# 20240714_smart_wheelchair.net
KiCad netlist of a schematic drawn in Altium Designer
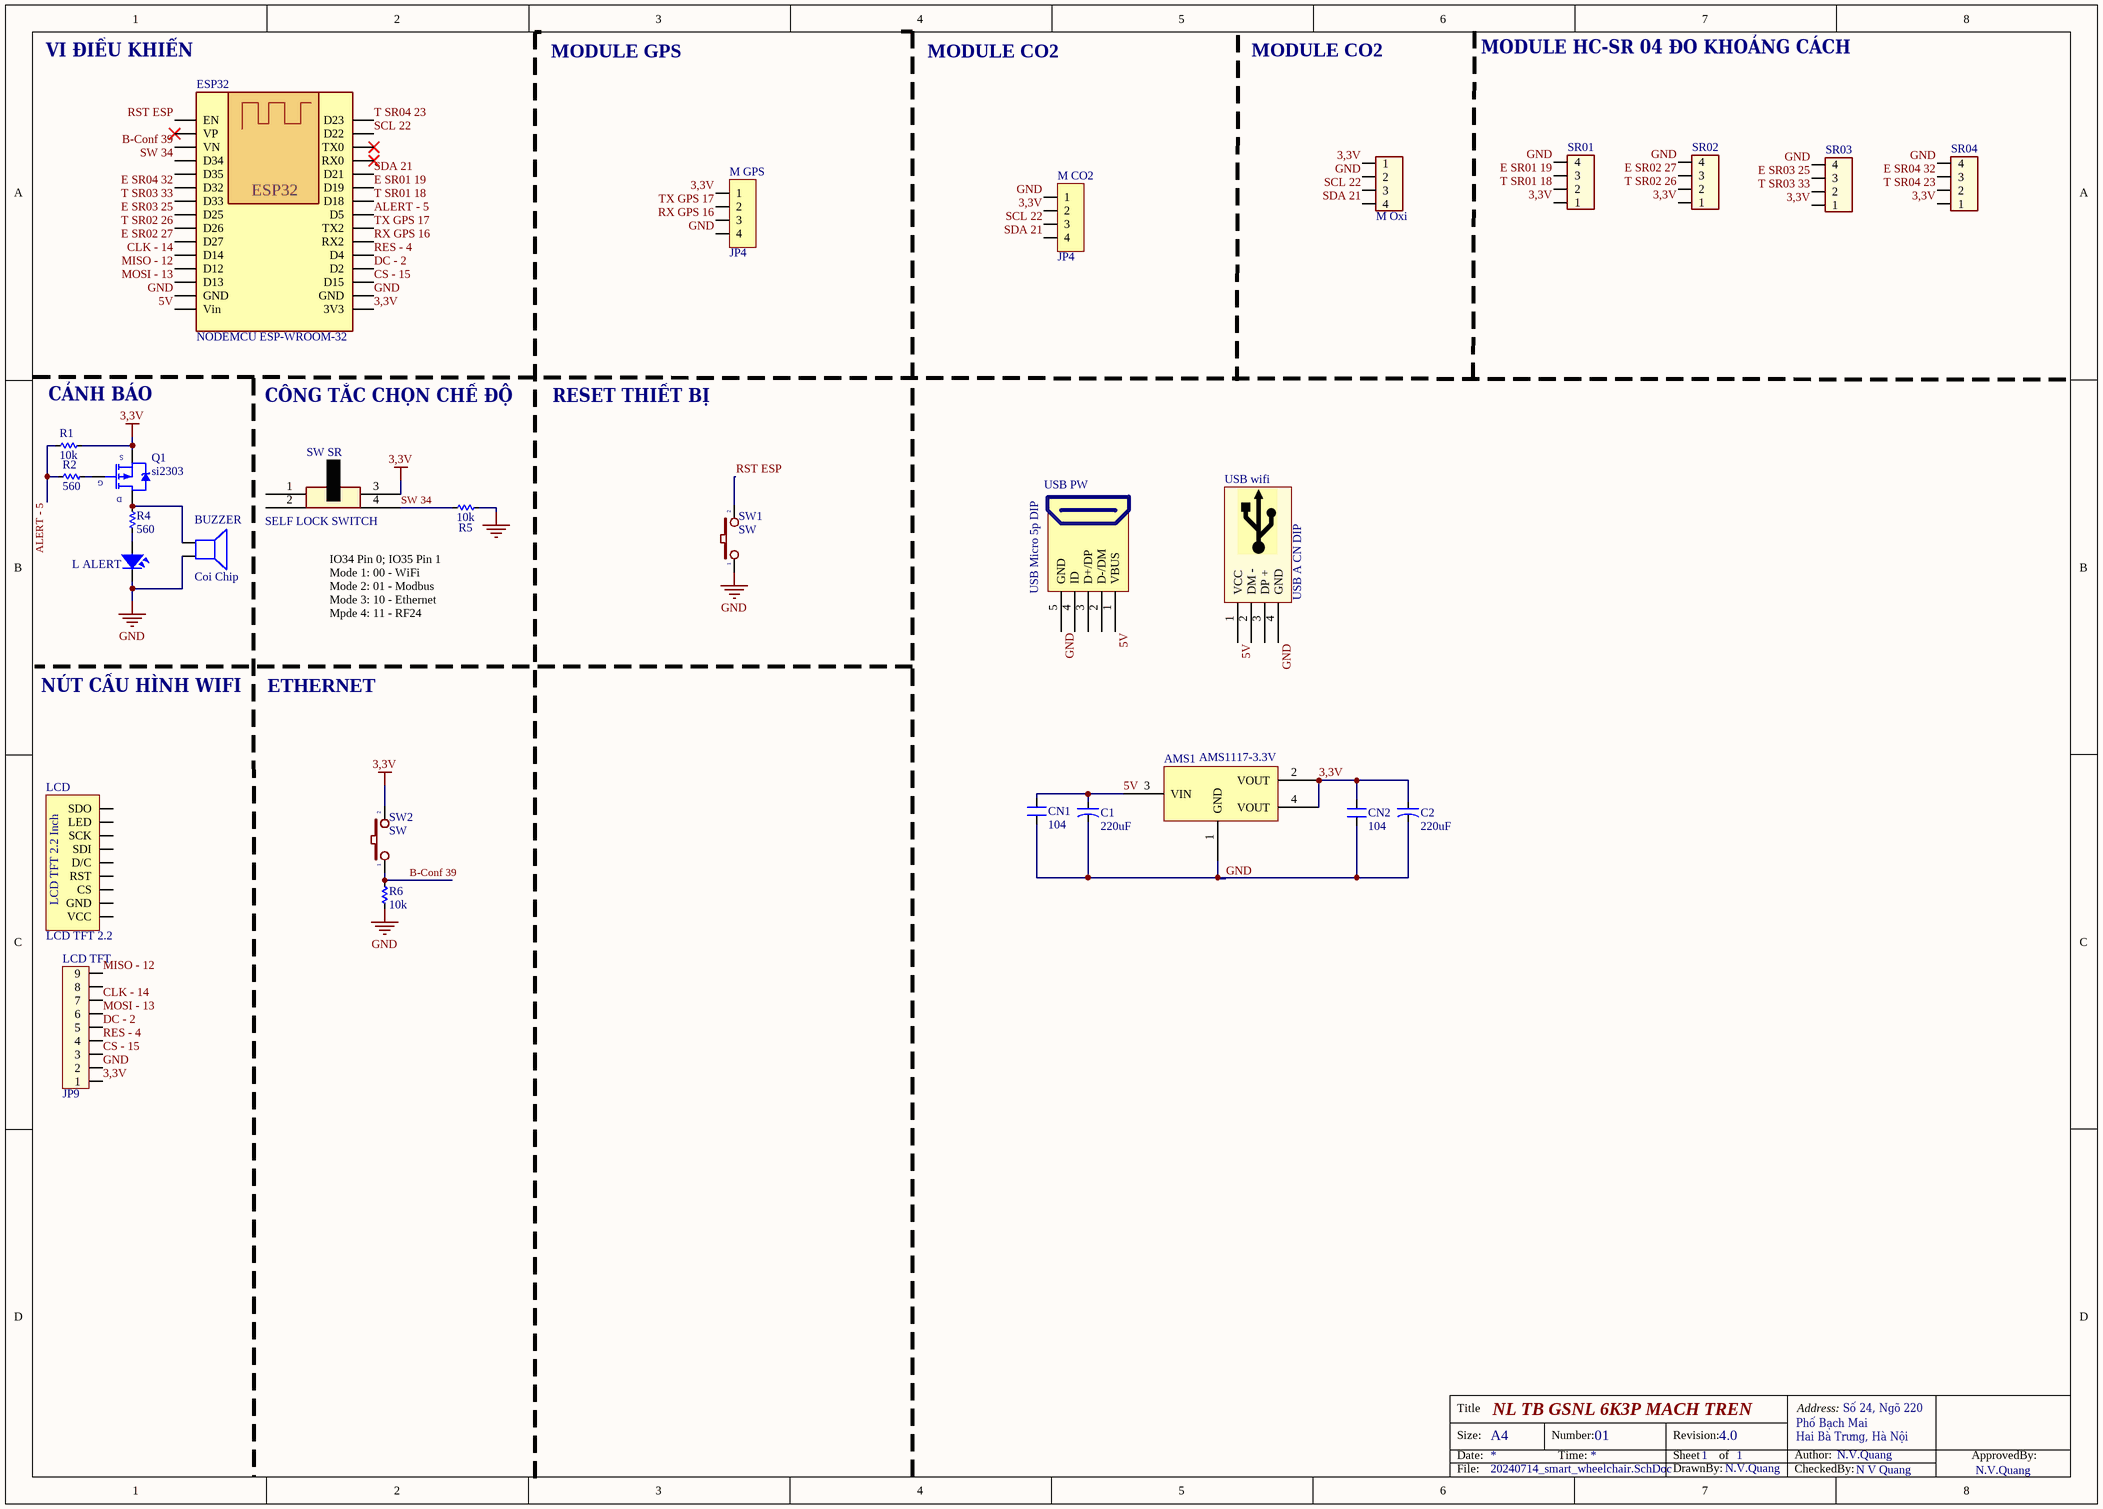
[diagram p0: 20240714_smart_wheelchair.SchDoc]

(export (version "E")
  (design (tool "Eeschema 10.0.6"))
  (components
    (comp (ref "AMS1")
      (value "AMS1117-3.3V")
      (footprint "SOT223")
      (description "Dán")
      (libsource (lib "Altium_Lib") (part "AMS1117 SMD"))
    )
    (comp (ref "BUZZER")
      (value "Coi Chip")
      (footprint "Coi Chip Speacker")
      (description "Còi chip")
      (libsource (lib "Altium_Lib") (part "Coi Chip Speaker"))
    )
    (comp (ref "C1")
      (value "220uF")
      (footprint "CA-ALU-5")
      (description "Capacitor (Semiconductor SIM Model)")
      (fields (field (name "PUBLISHER") "Altium Limited"))
      (libsource (lib "LIBRARY") (part "CN-ALU-DIP"))
    )
    (comp (ref "C2")
      (value "220uF")
      (footprint "CA-ALU-5")
      (description "Capacitor (Semiconductor SIM Model)")
      (fields (field (name "PUBLISHER") "Altium Limited"))
      (libsource (lib "LIBRARY") (part "CN-ALU-DIP"))
    )
    (comp (ref "CN1")
      (value "104")
      (footprint "SM-CAP-0805")
      (description "0805; 0603")
      (libsource (lib "Altium_Lib") (part "CN"))
    )
    (comp (ref "CN2")
      (value "104")
      (footprint "SM-CAP-0805")
      (description "0805; 0603")
      (libsource (lib "Altium_Lib") (part "CN"))
    )
    (comp (ref "ESP32")
      (value "NODEMCU ESP-WROOM-32")
      (footprint "NODEMCU ESP-WROOM-32")
      (libsource (lib "Quang lib") (part "NODEMCU ESP-WROOM-32"))
    )
    (comp (ref "L ALERT")
      (value "LED")
      (footprint "LED-5MM-RED")
      (description "LED Single colour Green and Red")
      (libsource (lib "LIBRARY") (part "LED"))
    )
    (comp (ref "LCD")
      (value "LCD TFT 2.2")
      (footprint "LCD TFT 2.2")
      (fields
        (field (name "MANUFACTURER") "Würth Elektronik eiSos GmbH")
        (field (name "PARTNO") "613009143121")
        (field (name "CREATED BY") "Karrer Zheng")
      )
      (libsource (lib "LIBRARY") (part "LCD TFT 2.2"))
    )
    (comp (ref "LCD TFT")
      (value "JP9")
      (footprint "Header9")
      (description "Connector 9")
      (libsource (lib "LIBRARY") (part "Header9"))
    )
    (comp (ref "M CO2")
      (value "JP4")
      (footprint "JP4-C1T")
      (description "WR-PHD 2.54 mm Angled Socket Header")
      (fields
        (field (name "MANUFACTURER") "Würth Elektronik eiSos GmbH")
        (field (name "PARTNO") "613004143121")
        (field (name "CREATED BY") "Karrer Zheng")
      )
      (libsource (lib "LIBRARY") (part "JP4"))
    )
    (comp (ref "M GPS")
      (value "JP4")
      (footprint "JP4-C1T")
      (description "WR-PHD 2.54 mm Angled Socket Header")
      (fields
        (field (name "MANUFACTURER") "Würth Elektronik eiSos GmbH")
        (field (name "PARTNO") "613004143121")
        (field (name "CREATED BY") "Karrer Zheng")
      )
      (libsource (lib "LIBRARY") (part "JP4"))
    )
    (comp (ref "M Oxi")
      (value "HP4")
      (footprint "Header4P Cong")
      (description "Header4P")
      (libsource (lib "Altium_Lib") (part "Header4P"))
    )
    (comp (ref "Q1")
      (value "si2303")
      (footprint "si2303 - duplicate")
      (libsource (lib "Altium_Lib") (part "Si2303"))
    )
    (comp (ref "R1")
      (value "10k")
      (footprint "RES-SMD-0805")
      (description "Resistor")
      (fields
        (field (name "MANUFACTURER") "Generic Components")
        (field (name "PUBLISHER") "Altium Hobart Technology Centre")
      )
      (libsource (lib "LIBRARY") (part "Res-SMD"))
    )
    (comp (ref "R2")
      (value "560")
      (footprint "RES-SMD-0805")
      (description "Resistor")
      (fields
        (field (name "MANUFACTURER") "Generic Components")
        (field (name "PUBLISHER") "Altium Hobart Technology Centre")
      )
      (libsource (lib "LIBRARY") (part "Res-SMD"))
    )
    (comp (ref "R4")
      (value "560")
      (footprint "RES-SMD-0805")
      (description "Resistor")
      (fields
        (field (name "MANUFACTURER") "Generic Components")
        (field (name "PUBLISHER") "Altium Hobart Technology Centre")
      )
      (libsource (lib "LIBRARY") (part "Res-SMD"))
    )
    (comp (ref "R5")
      (value "10k")
      (footprint "RES-SMD-0805")
      (description "Resistor")
      (fields
        (field (name "MANUFACTURER") "Generic Components")
        (field (name "PUBLISHER") "Altium Hobart Technology Centre")
      )
      (libsource (lib "LIBRARY") (part "Res-SMD"))
    )
    (comp (ref "R6")
      (value "10k")
      (footprint "RES-SMD-0805")
      (description "Resistor")
      (fields
        (field (name "MANUFACTURER") "Generic Components")
        (field (name "PUBLISHER") "Altium Hobart Technology Centre")
      )
      (libsource (lib "LIBRARY") (part "Res-SMD"))
    )
    (comp (ref "SR01")
      (value "HP4")
      (footprint "Header4P Cong")
      (description "Header4P")
      (libsource (lib "") (part "Header4P_1"))
    )
    (comp (ref "SR02")
      (value "HP4")
      (footprint "Header4P Cong")
      (description "Header4P")
      (libsource (lib "") (part "Header4P_1"))
    )
    (comp (ref "SR03")
      (value "HP4")
      (footprint "Header4P Cong")
      (description "Header4P")
      (libsource (lib "") (part "Header4P_1"))
    )
    (comp (ref "SR04")
      (value "HP4")
      (footprint "Header4P Cong")
      (description "Header4P")
      (libsource (lib "") (part "Header4P_1"))
    )
    (comp (ref "SW SR")
      (value "SELF LOCK SWITCH")
      (footprint "SW_70_31.5D47_TH_ST")
      (description "6 Pin DPDT Mini Push Button Self-locking Switch Multimeter Switch")
      (fields (field (name "MANUFACTURER PART NUMBER") "NA"))
      (libsource (lib "Altium_Lib") (part "SW1_LOCAL-TH"))
    )
    (comp (ref "SW1")
      (value "SW")
      (footprint "SW1-DIP")
      (description "Switch button 2 pin")
      (libsource (lib "LIBRARY") (part "SW2"))
    )
    (comp (ref "SW2")
      (value "SW")
      (footprint "SW1-DIP")
      (description "Switch button 2 pin")
      (libsource (lib "LIBRARY") (part "SW2"))
    )
    (comp (ref "USB PW")
      (value "USB Micro 5p DIP")
      (footprint "USB Micro 5p DIP")
      (description "USB Type B")
      (libsource (lib "Altium_Lib") (part "USB Micro 5p DIP"))
    )
    (comp (ref "USB wifi")
      (value "USB A CN DIP")
      (footprint "USB A CN DIP")
      (description "USB Type A")
      (libsource (lib "Altium_Lib") (part "USB A CN DIP"))
    )
  )
  (nets
    (net (code "1") (name "/5V") (class "Default")
      (node (ref "AMS1") (pin "3") (pinfunction "VIN_3") (pintype "passive"))
      (node (ref "C1") (pin "1") (pinfunction "1_1") (pintype "passive"))
      (node (ref "CN1") (pin "2") (pinfunction "2_2") (pintype "passive"))
      (node (ref "ESP32") (pin "15") (pinfunction "Vin_15") (pintype "passive"))
      (node (ref "USB PW") (pin "1") (pinfunction "VBUS_1") (pintype "passive"))
      (node (ref "USB wifi") (pin "1") (pinfunction "VCC_1") (pintype "passive"))
    )
    (net (code "2") (name "/ALERT - 5") (class "Default")
      (node (ref "ESP32") (pin "23") (pinfunction "D5_23") (pintype "passive"))
      (node (ref "R1") (pin "2") (pinfunction "2_2") (pintype "passive"))
      (node (ref "R2") (pin "2") (pinfunction "2_2") (pintype "passive"))
    )
    (net (code "3") (name "/B-Conf 39") (class "Default")
      (node (ref "ESP32") (pin "3") (pinfunction "VN_3") (pintype "passive"))
      (node (ref "R6") (pin "1") (pinfunction "1_1") (pintype "passive"))
      (node (ref "SW2") (pin "1") (pinfunction "1_1") (pintype "passive"))
    )
    (net (code "4") (name "/CLK - 14") (class "Default")
      (node (ref "ESP32") (pin "11") (pinfunction "D14_11") (pintype "passive"))
      (node (ref "LCD TFT") (pin "7") (pinfunction "7_7") (pintype "passive"))
    )
    (net (code "5") (name "/CS - 15") (class "Default")
      (node (ref "ESP32") (pin "18") (pinfunction "D15_18") (pintype "passive"))
      (node (ref "LCD TFT") (pin "3") (pinfunction "3_3") (pintype "passive"))
    )
    (net (code "6") (name "/DC - 2") (class "Default")
      (node (ref "ESP32") (pin "19") (pinfunction "D2_19") (pintype "passive"))
      (node (ref "LCD TFT") (pin "5") (pinfunction "5_5") (pintype "passive"))
    )
    (net (code "7") (name "/E SR01 19") (class "Default")
      (node (ref "ESP32") (pin "25") (pinfunction "D19_25") (pintype "passive"))
      (node (ref "SR01") (pin "3") (pinfunction "3_3") (pintype "passive"))
    )
    (net (code "8") (name "/E SR02 27") (class "Default")
      (node (ref "ESP32") (pin "10") (pinfunction "D27_10") (pintype "passive"))
      (node (ref "SR02") (pin "3") (pinfunction "3_3") (pintype "passive"))
    )
    (net (code "9") (name "/E SR03 25") (class "Default")
      (node (ref "ESP32") (pin "8") (pinfunction "D25_8") (pintype "passive"))
      (node (ref "SR03") (pin "3") (pinfunction "3_3") (pintype "passive"))
    )
    (net (code "10") (name "/E SR04 32") (class "Default")
      (node (ref "ESP32") (pin "6") (pinfunction "D32_6") (pintype "passive"))
      (node (ref "SR04") (pin "3") (pinfunction "3_3") (pintype "passive"))
    )
    (net (code "11") (name "/MISO - 12") (class "Default")
      (node (ref "ESP32") (pin "12") (pinfunction "D12_12") (pintype "passive"))
      (node (ref "LCD TFT") (pin "9") (pinfunction "9_9") (pintype "passive"))
    )
    (net (code "12") (name "/MOSI - 13") (class "Default")
      (node (ref "ESP32") (pin "13") (pinfunction "D13_13") (pintype "passive"))
      (node (ref "LCD TFT") (pin "6") (pinfunction "6_6") (pintype "passive"))
    )
    (net (code "13") (name "/RES - 4") (class "Default")
      (node (ref "ESP32") (pin "20") (pinfunction "D4_20") (pintype "passive"))
      (node (ref "LCD TFT") (pin "4") (pinfunction "4_4") (pintype "passive"))
    )
    (net (code "14") (name "/RST ESP") (class "Default")
      (node (ref "ESP32") (pin "1") (pinfunction "EN_1") (pintype "passive"))
      (node (ref "SW1") (pin "2") (pinfunction "2_2") (pintype "passive"))
    )
    (net (code "15") (name "/RX GPS 16") (class "Default")
      (node (ref "ESP32") (pin "21") (pinfunction "RX2_21") (pintype "passive"))
      (node (ref "M GPS") (pin "3") (pinfunction "3_3") (pintype "passive"))
    )
    (net (code "16") (name "/SCL 22") (class "Default")
      (node (ref "ESP32") (pin "29") (pinfunction "D22_29") (pintype "passive"))
      (node (ref "M CO2") (pin "3") (pinfunction "3_3") (pintype "passive"))
      (node (ref "M Oxi") (pin "3") (pinfunction "3_3") (pintype "passive"))
    )
    (net (code "17") (name "/SDA 21") (class "Default")
      (node (ref "ESP32") (pin "26") (pinfunction "D21_26") (pintype "passive"))
      (node (ref "M CO2") (pin "4") (pinfunction "4_4") (pintype "passive"))
      (node (ref "M Oxi") (pin "4") (pinfunction "4_4") (pintype "passive"))
    )
    (net (code "18") (name "/SW 34") (class "Default")
      (node (ref "ESP32") (pin "4") (pinfunction "D34_4") (pintype "passive"))
      (node (ref "R5") (pin "2") (pinfunction "2_2") (pintype "passive"))
      (node (ref "SW SR") (pin "4") (pinfunction "4_4") (pintype "passive"))
    )
    (net (code "19") (name "/T SR01 18") (class "Default")
      (node (ref "ESP32") (pin "24") (pinfunction "D18_24") (pintype "passive"))
      (node (ref "SR01") (pin "2") (pinfunction "2_2") (pintype "passive"))
    )
    (net (code "20") (name "/T SR02 26") (class "Default")
      (node (ref "ESP32") (pin "9") (pinfunction "D26_9") (pintype "passive"))
      (node (ref "SR02") (pin "2") (pinfunction "2_2") (pintype "passive"))
    )
    (net (code "21") (name "/T SR03 33") (class "Default")
      (node (ref "ESP32") (pin "7") (pinfunction "D33_7") (pintype "passive"))
      (node (ref "SR03") (pin "2") (pinfunction "2_2") (pintype "passive"))
    )
    (net (code "22") (name "/T SR04 23") (class "Default")
      (node (ref "ESP32") (pin "30") (pinfunction "D23_30") (pintype "passive"))
      (node (ref "SR04") (pin "2") (pinfunction "2_2") (pintype "passive"))
    )
    (net (code "23") (name "/TX GPS 17") (class "Default")
      (node (ref "ESP32") (pin "22") (pinfunction "TX2_22") (pintype "passive"))
      (node (ref "M GPS") (pin "2") (pinfunction "2_2") (pintype "passive"))
    )
    (net (code "24") (name "3,3V") (class "Default")
      (node (ref "AMS1") (pin "2") (pinfunction "VOUT_2") (pintype "passive"))
      (node (ref "AMS1") (pin "4") (pinfunction "VOUT_4") (pintype "passive"))
      (node (ref "C2") (pin "1") (pinfunction "1_1") (pintype "passive"))
      (node (ref "CN2") (pin "2") (pinfunction "2_2") (pintype "passive"))
      (node (ref "ESP32") (pin "16") (pinfunction "3V3_16") (pintype "passive"))
      (node (ref "LCD TFT") (pin "1") (pinfunction "1_1") (pintype "passive"))
      (node (ref "M CO2") (pin "2") (pinfunction "2_2") (pintype "passive"))
      (node (ref "M GPS") (pin "1") (pinfunction "1_1") (pintype "passive"))
      (node (ref "M Oxi") (pin "1") (pinfunction "1_1") (pintype "passive"))
      (node (ref "Q1") (pin "2") (pinfunction "S_2") (pintype "passive"))
      (node (ref "R1") (pin "1") (pinfunction "1_1") (pintype "passive"))
      (node (ref "SR01") (pin "1") (pinfunction "1_1") (pintype "passive"))
      (node (ref "SR02") (pin "1") (pinfunction "1_1") (pintype "passive"))
      (node (ref "SR03") (pin "1") (pinfunction "1_1") (pintype "passive"))
      (node (ref "SR04") (pin "1") (pinfunction "1_1") (pintype "passive"))
      (node (ref "SW SR") (pin "3") (pinfunction "3_3") (pintype "passive"))
      (node (ref "SW2") (pin "2") (pinfunction "2_2") (pintype "passive"))
    )
    (net (code "25") (name "GND") (class "Default")
      (node (ref "AMS1") (pin "1") (pinfunction "GND_1") (pintype "passive"))
      (node (ref "BUZZER") (pin "2") (pinfunction "2_2") (pintype "passive"))
      (node (ref "C1") (pin "2") (pinfunction "2_2") (pintype "passive"))
      (node (ref "C2") (pin "2") (pinfunction "2_2") (pintype "passive"))
      (node (ref "CN1") (pin "1") (pinfunction "1_1") (pintype "passive"))
      (node (ref "CN2") (pin "1") (pinfunction "1_1") (pintype "passive"))
      (node (ref "ESP32") (pin "14") (pinfunction "GND_14") (pintype "passive"))
      (node (ref "ESP32") (pin "17") (pinfunction "GND_17") (pintype "passive"))
      (node (ref "L ALERT") (pin "2") (pinfunction "2_2") (pintype "passive"))
      (node (ref "LCD TFT") (pin "2") (pinfunction "2_2") (pintype "passive"))
      (node (ref "M CO2") (pin "1") (pinfunction "1_1") (pintype "passive"))
      (node (ref "M GPS") (pin "4") (pinfunction "4_4") (pintype "passive"))
      (node (ref "M Oxi") (pin "2") (pinfunction "2_2") (pintype "passive"))
      (node (ref "R5") (pin "1") (pinfunction "1_1") (pintype "passive"))
      (node (ref "R6") (pin "2") (pinfunction "2_2") (pintype "passive"))
      (node (ref "SR01") (pin "4") (pinfunction "4_4") (pintype "passive"))
      (node (ref "SR02") (pin "4") (pinfunction "4_4") (pintype "passive"))
      (node (ref "SR03") (pin "4") (pinfunction "4_4") (pintype "passive"))
      (node (ref "SR04") (pin "4") (pinfunction "4_4") (pintype "passive"))
      (node (ref "SW1") (pin "1") (pinfunction "1_1") (pintype "passive"))
      (node (ref "USB PW") (pin "5") (pinfunction "GND_5") (pintype "passive"))
      (node (ref "USB wifi") (pin "4") (pinfunction "GND_4") (pintype "passive"))
    )
    (net (code "26") (name "Net-(L ALERT-Pad1)") (class "Default")
      (node (ref "L ALERT") (pin "1") (pinfunction "1_1") (pintype "passive"))
      (node (ref "R4") (pin "2") (pinfunction "2_2") (pintype "passive"))
    )
    (net (code "27") (name "Net-(Q1-D)") (class "Default")
      (node (ref "BUZZER") (pin "1") (pinfunction "1_1") (pintype "passive"))
      (node (ref "Q1") (pin "3") (pinfunction "D_3") (pintype "passive"))
      (node (ref "R4") (pin "1") (pinfunction "1_1") (pintype "passive"))
    )
    (net (code "28") (name "Net-(Q1-G)") (class "Default")
      (node (ref "Q1") (pin "1") (pinfunction "G_1") (pintype "passive"))
      (node (ref "R2") (pin "1") (pinfunction "1_1") (pintype "passive"))
    )
    (net (code "29") (name "unconnected-(ESP32-D35-Pad5)") (class "Default")
      (node (ref "ESP32") (pin "5") (pinfunction "D35_5") (pintype "passive"))
    )
    (net (code "30") (name "unconnected-(ESP32-RX0-Pad27)") (class "Default")
      (node (ref "ESP32") (pin "27") (pinfunction "RX0_27") (pintype "passive+no_connect"))
    )
    (net (code "31") (name "unconnected-(ESP32-TX0-Pad28)") (class "Default")
      (node (ref "ESP32") (pin "28") (pinfunction "TX0_28") (pintype "passive+no_connect"))
    )
    (net (code "32") (name "unconnected-(ESP32-VP-Pad2)") (class "Default")
      (node (ref "ESP32") (pin "2") (pinfunction "VP_2") (pintype "passive+no_connect"))
    )
    (net (code "33") (name "unconnected-(LCD TFT-Pad8)") (class "Default")
      (node (ref "LCD TFT") (pin "8") (pinfunction "8_8") (pintype "passive"))
    )
    (net (code "34") (name "unconnected-(LCD-CS-Pad3)") (class "Default")
      (node (ref "LCD") (pin "3") (pinfunction "CS_3") (pintype "passive"))
    )
    (net (code "35") (name "unconnected-(LCD-D{slash}C-Pad5)") (class "Default")
      (node (ref "LCD") (pin "5") (pinfunction "D/C_5") (pintype "passive"))
    )
    (net (code "36") (name "unconnected-(LCD-GND-Pad2)") (class "Default")
      (node (ref "LCD") (pin "2") (pinfunction "GND_2") (pintype "passive"))
    )
    (net (code "37") (name "unconnected-(LCD-LED-Pad8)") (class "Default")
      (node (ref "LCD") (pin "8") (pinfunction "LED_8") (pintype "passive"))
    )
    (net (code "38") (name "unconnected-(LCD-RST-Pad4)") (class "Default")
      (node (ref "LCD") (pin "4") (pinfunction "RST_4") (pintype "passive"))
    )
    (net (code "39") (name "unconnected-(LCD-SCK-Pad7)") (class "Default")
      (node (ref "LCD") (pin "7") (pinfunction "SCK_7") (pintype "passive"))
    )
    (net (code "40") (name "unconnected-(LCD-SDI-Pad6)") (class "Default")
      (node (ref "LCD") (pin "6") (pinfunction "SDI_6") (pintype "passive"))
    )
    (net (code "41") (name "unconnected-(LCD-SDO-Pad9)") (class "Default")
      (node (ref "LCD") (pin "9") (pinfunction "SDO_9") (pintype "passive"))
    )
    (net (code "42") (name "unconnected-(LCD-VCC-Pad1)") (class "Default")
      (node (ref "LCD") (pin "1") (pinfunction "VCC_1") (pintype "passive"))
    )
    (net (code "43") (name "unconnected-(SW SR-Pad1)") (class "Default")
      (node (ref "SW SR") (pin "1") (pinfunction "1_1") (pintype "passive"))
    )
    (net (code "44") (name "unconnected-(SW SR-Pad2)") (class "Default")
      (node (ref "SW SR") (pin "2") (pinfunction "2_2") (pintype "passive"))
    )
    (net (code "45") (name "unconnected-(USB PW-D+{slash}DP-Pad3)") (class "Default")
      (node (ref "USB PW") (pin "3") (pinfunction "D+/DP_3") (pintype "passive"))
    )
    (net (code "46") (name "unconnected-(USB PW-D-{slash}DM-Pad2)") (class "Default")
      (node (ref "USB PW") (pin "2") (pinfunction "D-/DM_2") (pintype "passive"))
    )
    (net (code "47") (name "unconnected-(USB PW-ID-Pad4)") (class "Default")
      (node (ref "USB PW") (pin "4") (pinfunction "ID_4") (pintype "passive"))
    )
    (net (code "48") (name "unconnected-(USB wifi-DM_--Pad2)") (class "Default")
      (node (ref "USB wifi") (pin "2") (pinfunction "DM_-_2") (pintype "passive"))
    )
    (net (code "49") (name "unconnected-(USB wifi-DP_+-Pad3)") (class "Default")
      (node (ref "USB wifi") (pin "3") (pinfunction "DP_+_3") (pintype "passive"))
    )
  )
)
